# Power_-_Switch_Power.net
KiCad netlist of a schematic drawn in Altium Designer
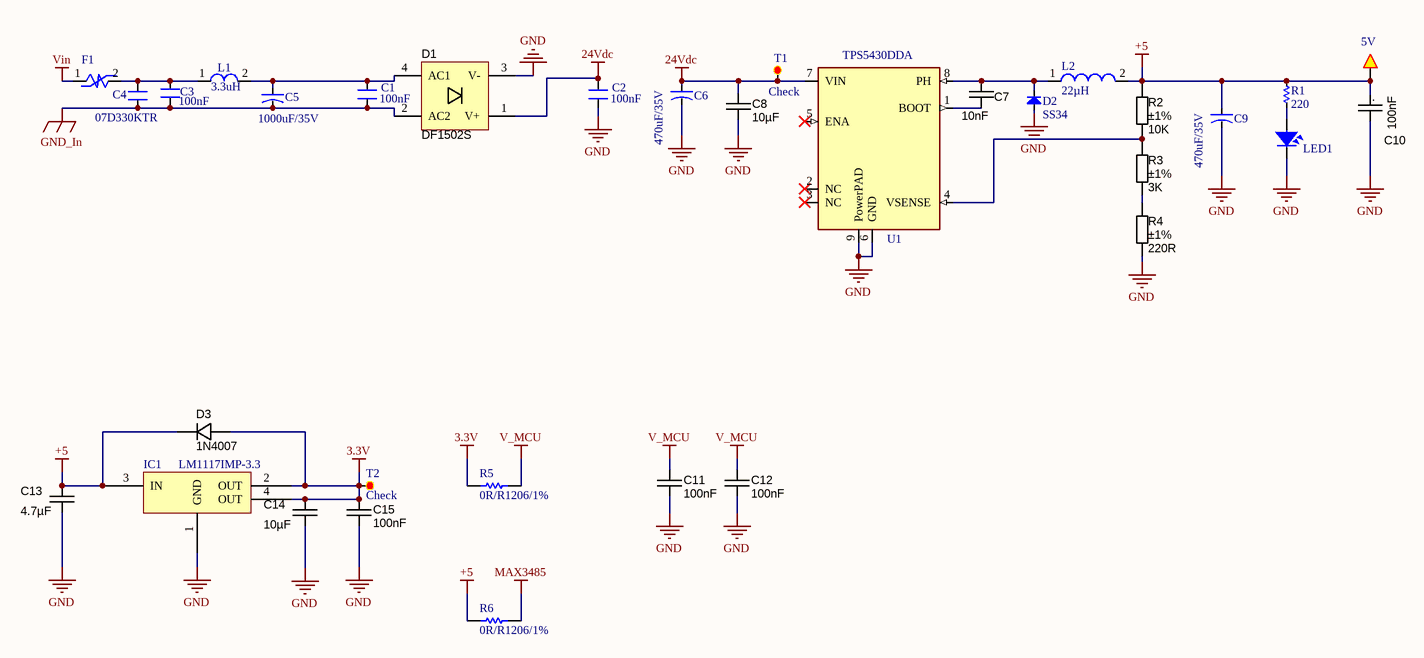
[diagram p0: Power - Switch Power.SchDoc]

(export (version "E")
  (design (tool "Eeschema 10.0.6"))
  (components
    (comp (ref "C1") (value "100nF") (footprint "CN-SMD-1206") (libsource (lib "thu vien 3d") (part "CN")))
    (comp (ref "C2") (value "100nF") (footprint "CN-SMD-1206") (libsource (lib "thu vien 3d") (part "CN")))
    (comp (ref "C3") (value "100nF") (footprint "CN2.5") (libsource (lib "thu vien 3d") (part "CN")))
    (comp (ref "C4") (value "07D330KTR") (footprint "CN2-T") (libsource (lib "thu vien 3d") (part "CN")))
    (comp (ref "C5")
      (value "1000uF/35V")
      (footprint "CA-ALU-5L")
      (description "Capacitor (Semiconductor SIM Model)")
      (fields (field (name "PUBLISHER") "Altium Limited"))
      (libsource (lib "thu vien 3d") (part "CN-ALU-DIP"))
    )
    (comp (ref "C6")
      (value "470uF/35V")
      (footprint "CA-ALU-6.3")
      (description "Capacitor (Semiconductor SIM Model)")
      (fields (field (name "PUBLISHER") "Altium Limited"))
      (libsource (lib "thu vien 3d") (part "CN-ALU-DIP"))
    )
    (comp (ref "C7")
      (value "10nF")
      (footprint "CAPC1608X90N")
      (description "10000pF ±10% 50V Ceramic Capacitor X7R 0603 (1608 Metric)")
      (fields (field (name "TOLERANCE") "±10%"))
      (libsource (lib "SangMV") (part "CAPC_10000pF_0603_50V_10%"))
    )
    (comp (ref "C8")
      (value "10µF")
      (footprint "CAPC2012X135N")
      (description "10µF ±10% 50V Ceramic Capacitor X7R 1206 (3216 Metric)")
      (fields (field (name "TOLERANCE") "±10%") (field (name "MANUFACTURER PART NUMBER") "TMK316AB7106KLHT"))
      (libsource (lib "All Library") (part "CAPC_10uF_0805_X7R_25V_10%"))
    )
    (comp (ref "C9")
      (value "470uF/35V")
      (footprint "CA-ALU-6.3")
      (description "Capacitor (Semiconductor SIM Model)")
      (fields (field (name "PUBLISHER") "Altium Limited"))
      (libsource (lib "thu vien 3d") (part "CN-ALU-DIP"))
    )
    (comp (ref "C10")
      (value "100nF")
      (footprint "CAPC2012X135N")
      (description "0.1µF ±10% 50V Ceramic Capacitor X7R 0805 (2012 Metric)")
      (fields (field (name "TOLERANCE") "±10%") (field (name "MANUFACTURER PART NUMBER") "CL21B104KBFXPJE"))
      (libsource (lib "SangMV") (part "CAPC_100nF_0805_X7R_50V_10%"))
    )
    (comp (ref "C11")
      (value "100nF")
      (footprint "CAPC1608X90N")
      (description "0.1µF ±10% 50V Ceramic Capacitor X7R 0603 (1608 Metric)")
      (fields (field (name "TOLERANCE") "±10%"))
      (libsource (lib "All Library") (part "CAPC_100nF_0603_X7R_50V_10%"))
    )
    (comp (ref "C12")
      (value "100nF")
      (footprint "CAPC1608X90N")
      (description "0.1µF ±10% 50V Ceramic Capacitor X7R 0603 (1608 Metric)")
      (fields (field (name "TOLERANCE") "±10%"))
      (libsource (lib "All Library") (part "CAPC_100nF_0603_X7R_50V_10%"))
    )
    (comp (ref "C13")
      (value "4.7µF")
      (footprint "CAPC2012X135N")
      (description "4.7µF ±10% 50V Ceramic Capacitor X7R 0805 (2012 Metric)")
      (fields
        (field (name "TOLERANCE") "±10%")
        (field (name "MANUFACTURER PART NUMBER") "CGA4J1X7R1H475K125AE")
      )
      (libsource (lib "All Library") (part "CAPC_4.7uF_0805_X7R_50V_10%"))
    )
    (comp (ref "C14")
      (value "10µF")
      (footprint "CAPC2012X135N")
      (description "4.7µF ±10% 50V Ceramic Capacitor X7R 0805 (2012 Metric)")
      (fields
        (field (name "TOLERANCE") "±10%")
        (field (name "MANUFACTURER PART NUMBER") "CGA4J1X7R1H475K125AE")
      )
      (libsource (lib "All Library") (part "CAPC_4.7uF_0805_X7R_50V_10%"))
    )
    (comp (ref "C15")
      (value "100nF")
      (footprint "CAPC1608X90N")
      (description "0.1µF ±10% 50V Ceramic Capacitor X7R 0603 (1608 Metric)")
      (fields (field (name "TOLERANCE") "±10%"))
      (libsource (lib "All Library") (part "CAPC_100nF_0603_X7R_50V_10%"))
    )
    (comp (ref "Check1")
      (value "5V")
      (footprint "SMD-2")
      (description "WR-PHD 2.54 mm Angled Socket Header")
      (fields
        (field (name "MANUFACTURER") "Würth Elektronik eiSos GmbH")
        (field (name "PARTNO") "613002143121")
        (field (name "CREATED BY") "Karrer Zheng")
      )
      (libsource (lib "Nichietsuvn") (part "Test"))
    )
    (comp (ref "D1")
      (value "DF1502S")
      (footprint "DIODE_DF_S")
      (description "Bridge Rectifier Single Phase Standard 200V Surface Mount DF-S")
      (libsource (lib "PCB_ESP32_Extern") (part "DIODE_DF1502S"))
    )
    (comp (ref "D2")
      (value "SS34")
      (footprint "DIO-SMD-106")
      (description "Default Diode")
      (fields (field (name "PUBLISHER") "Altium Limited"))
      (libsource (lib "thu vien 3d") (part "Diode SMD"))
    )
    (comp (ref "D3")
      (value "1N4007")
      (footprint "DO-214AC")
      (description "Diode  Standard Rectifier SMD 1000V 1A SMA")
      (libsource (lib "All Library") (part "DIODE_1N4007"))
    )
    (comp (ref "F1") (value "RUEF185") (footprint "RUEF165") (libsource (lib "All Library") (part "RUEF185")))
    (comp (ref "IC1")
      (value "LM1117IMP-3.3")
      (footprint "SOT223")
      (description "Linear Voltage Regulator IC  1 Output  800mA SOT-223")
      (fields
        (field (name "MANUFACTURER") "Texas Instruments")
        (field (name "MANUFACTURER PART NUMBER") "LM1117IMP-3.3/NOPB")
      )
      (libsource (lib "All Library") (part "IC_LM1117IMP-3.3"))
    )
    (comp (ref "L1")
      (value "3.3uH")
      (footprint "L-SMD-M-7.3x4.5")
      (fields
        (field (name "PARTNO") "78477010")
        (field (name "MANUFACTURER") "Wurth Elektronik")
        (field (name "CREATED BY") "Baojun Chen")
      )
      (libsource (lib "thu vien 3d") (part "L-SMD-1"))
    )
    (comp (ref "L2")
      (value "22µH")
      (footprint "IND_COIL_8D43")
      (description "22µH Shielded Wirewound Inductor 950mA 380mOhm Max Nonstandard")
      (libsource (lib "SangMV") (part "INDC_SMD_22uH_8D43"))
    )
    (comp (ref "LED1")
      (value "LED")
      (footprint "LED-0805-Blue")
      (libsource (lib "thu vien 3d") (part "LED SMD"))
    )
    (comp (ref "R1")
      (value "220")
      (footprint "RES-SMD-0603")
      (description "Resistor")
      (fields
        (field (name "MANUFACTURER") "Generic Components")
        (field (name "PUBLISHER") "Altium Hobart Technology Centre")
      )
      (libsource (lib "thu vien 3d") (part "Res-SMD"))
    )
    (comp (ref "R2")
      (value "10K")
      (footprint "RESC1608X55N")
      (fields
        (field (name "MANUFACTURER") "Stackpole Electronics Inc")
        (field (name "MANUFACTURER PART NUMBER") "RMCF0603FT10K0")
        (field (name "TOLERANCE") "±1%")
        (field (name "Comment") "10K_0603_1%")
      )
      (libsource (lib "SangMV") (part "RES_10K_0603_1%"))
    )
    (comp (ref "R3")
      (value "3K")
      (footprint "RESC1608X55N")
      (description "3 kOhms ±1% 0.1W, 1/10W Chip Resistor 0603 (1608 Metric) Automotive AEC-Q200 Thick Film")
      (fields
        (field (name "MANUFACTURER") "Stackpole Electronics Inc")
        (field (name "MANUFACTURER PART NUMBER") "RMCF0603FT3K00")
        (field (name "TOLERANCE") "±1%")
      )
      (libsource (lib "SangMV") (part "RES_3K_0603_1%"))
    )
    (comp (ref "R4")
      (value "220R")
      (footprint "RESC1608X55N")
      (description "220 Ohms ±1% 0.1W, 1/10W Chip Resistor 0603 (1608 Metric) Automotive AEC-Q200 Thick Film")
      (fields
        (field (name "MANUFACTURER") "Stackpole Electronics Inc")
        (field (name "MANUFACTURER PART NUMBER") "RMCF0603FT220R")
        (field (name "TOLERANCE") "±1%")
      )
      (libsource (lib "SangMV") (part "RES_220R_0603_1%"))
    )
    (comp (ref "R5")
      (value "0R/R1206/1%")
      (footprint "R1206")
      (description "RES SMD 0.0 OHM JUMPER 1/4W 1206")
      (fields
        (field (name "MANUFACTURER") "Bourns Inc.")
        (field (name "MANUFACTURER PART NUMBER") "CR1206-J/-000ELF")
      )
      (libsource (lib "All Library") (part "RES_0R/R1206/1%"))
    )
    (comp (ref "R6")
      (value "0R/R1206/1%")
      (footprint "R1206")
      (description "RES SMD 0.0 OHM JUMPER 1/4W 1206")
      (fields
        (field (name "MANUFACTURER") "Bourns Inc.")
        (field (name "MANUFACTURER PART NUMBER") "CR1206-J/-000ELF")
      )
      (libsource (lib "All Library") (part "RES_0R/R1206/1%"))
    )
    (comp (ref "T1")
      (value "Check")
      (footprint "SMD_1.5")
      (description "WR-PHD 2.54 mm Angled Socket Header")
      (fields
        (field (name "MANUFACTURER") "Würth Elektronik eiSos GmbH")
        (field (name "PARTNO") "613002143121")
        (field (name "CREATED BY") "Karrer Zheng")
      )
      (libsource (lib "All Library") (part "Test"))
    )
    (comp (ref "T2")
      (value "Check")
      (footprint "SMD_1.5")
      (description "WR-PHD 2.54 mm Angled Socket Header")
      (fields
        (field (name "MANUFACTURER") "Würth Elektronik eiSos GmbH")
        (field (name "PARTNO") "613002143121")
        (field (name "CREATED BY") "Karrer Zheng")
      )
      (libsource (lib "All Library") (part "Test"))
    )
    (comp (ref "U1")
      (value "TPS5430DDA")
      (footprint "TPS5430")
      (libsource (lib "Nichietsuvn") (part "TPS5430DDA"))
    )
  )
  (nets
    (net (code "1") (name "+5") (class "Default")
      (node (ref "C10") (pin "1") (pintype "passive"))
      (node (ref "C13") (pin "2") (pintype "passive"))
      (node (ref "C9") (pin "1") (pinfunction "1_1") (pintype "passive"))
      (node (ref "Check1") (pin "1") (pinfunction "1_1") (pintype "passive"))
      (node (ref "D3") (pin "C") (pinfunction "C_C") (pintype "passive"))
      (node (ref "IC1") (pin "3") (pinfunction "IN_3") (pintype "passive"))
      (node (ref "L2") (pin "2") (pinfunction "2_2") (pintype "passive"))
      (node (ref "R1") (pin "1") (pinfunction "1_1") (pintype "passive"))
      (node (ref "R2") (pin "2") (pinfunction "2_2") (pintype "passive"))
      (node (ref "R6") (pin "1") (pinfunction "1_1") (pintype "passive"))
    )
    (net (code "2") (name "3.3V") (class "Default")
      (node (ref "C14") (pin "2") (pintype "passive"))
      (node (ref "C15") (pin "1") (pintype "passive"))
      (node (ref "D3") (pin "A") (pinfunction "A_A") (pintype "passive"))
      (node (ref "IC1") (pin "2") (pinfunction "OUT_2") (pintype "passive"))
      (node (ref "IC1") (pin "4") (pinfunction "OUT_4") (pintype "passive"))
      (node (ref "R5") (pin "1") (pinfunction "1_1") (pintype "passive"))
      (node (ref "T2") (pin "1") (pinfunction "1_1") (pintype "passive"))
    )
    (net (code "3") (name "24Vdc") (class "Default")
      (node (ref "C2") (pin "2") (pinfunction "2_2") (pintype "passive"))
      (node (ref "C6") (pin "1") (pinfunction "1_1") (pintype "passive"))
      (node (ref "C8") (pin "2") (pintype "passive"))
      (node (ref "D1") (pin "1") (pinfunction "V+_1") (pintype "passive"))
      (node (ref "T1") (pin "1") (pinfunction "1_1") (pintype "passive"))
      (node (ref "U1") (pin "7") (pinfunction "VIN_7") (pintype "power_in"))
    )
    (net (code "4") (name "GND") (class "Default")
      (node (ref "C10") (pin "2") (pintype "passive"))
      (node (ref "C11") (pin "2") (pintype "passive"))
      (node (ref "C12") (pin "2") (pintype "passive"))
      (node (ref "C13") (pin "1") (pintype "passive"))
      (node (ref "C14") (pin "1") (pintype "passive"))
      (node (ref "C15") (pin "2") (pintype "passive"))
      (node (ref "C2") (pin "1") (pinfunction "1_1") (pintype "passive"))
      (node (ref "C6") (pin "2") (pinfunction "2_2") (pintype "passive"))
      (node (ref "C8") (pin "1") (pintype "passive"))
      (node (ref "C9") (pin "2") (pinfunction "2_2") (pintype "passive"))
      (node (ref "D1") (pin "3") (pinfunction "V-_3") (pintype "passive"))
      (node (ref "D2") (pin "1") (pinfunction "A_1") (pintype "passive"))
      (node (ref "IC1") (pin "1") (pinfunction "GND_1") (pintype "passive"))
      (node (ref "LED1") (pin "2") (pinfunction "2_2") (pintype "passive"))
      (node (ref "R4") (pin "1") (pinfunction "1_1") (pintype "passive"))
      (node (ref "U1") (pin "6") (pinfunction "GND_6") (pintype "power_in"))
      (node (ref "U1") (pin "9") (pinfunction "PowerPAD_9") (pintype "power_in"))
    )
    (net (code "5") (name "GND_In") (class "Default")
      (node (ref "C1") (pin "1") (pinfunction "1_1") (pintype "passive"))
      (node (ref "C3") (pin "1") (pinfunction "1_1") (pintype "passive"))
      (node (ref "C4") (pin "1") (pinfunction "1_1") (pintype "passive"))
      (node (ref "C5") (pin "2") (pinfunction "2_2") (pintype "passive"))
      (node (ref "D1") (pin "2") (pinfunction "AC2_2") (pintype "passive"))
    )
    (net (code "6") (name "MAX3485") (class "Default")
      (node (ref "R6") (pin "2") (pinfunction "2_2") (pintype "passive"))
    )
    (net (code "7") (name "Net-(C3-Pad2)") (class "Default")
      (node (ref "C3") (pin "2") (pinfunction "2_2") (pintype "passive"))
      (node (ref "C4") (pin "2") (pinfunction "2_2") (pintype "passive"))
      (node (ref "F1") (pin "2") (pinfunction "2_2") (pintype "passive"))
      (node (ref "L1") (pin "1") (pinfunction "1_1") (pintype "passive"))
    )
    (net (code "8") (name "Net-(D1-AC1)") (class "Default")
      (node (ref "C1") (pin "2") (pinfunction "2_2") (pintype "passive"))
      (node (ref "C5") (pin "1") (pinfunction "1_1") (pintype "passive"))
      (node (ref "D1") (pin "4") (pinfunction "AC1_4") (pintype "passive"))
      (node (ref "L1") (pin "2") (pinfunction "2_2") (pintype "passive"))
    )
    (net (code "9") (name "Net-(D2-K)") (class "Default")
      (node (ref "C7") (pin "2") (pintype "passive"))
      (node (ref "D2") (pin "2") (pinfunction "K_2") (pintype "passive"))
      (node (ref "L2") (pin "1") (pinfunction "1_1") (pintype "passive"))
      (node (ref "U1") (pin "8") (pinfunction "PH_8") (pintype "input"))
    )
    (net (code "10") (name "Net-(LED1-Pad1)") (class "Default")
      (node (ref "LED1") (pin "1") (pinfunction "1_1") (pintype "passive"))
      (node (ref "R1") (pin "2") (pinfunction "2_2") (pintype "passive"))
    )
    (net (code "11") (name "Net-(R3-Pad1)") (class "Default")
      (node (ref "R3") (pin "1") (pinfunction "1_1") (pintype "passive"))
      (node (ref "R4") (pin "2") (pinfunction "2_2") (pintype "passive"))
    )
    (net (code "12") (name "Net-(U1-BOOT)") (class "Default")
      (node (ref "C7") (pin "1") (pintype "passive"))
      (node (ref "U1") (pin "1") (pinfunction "BOOT_1") (pintype "output"))
    )
    (net (code "13") (name "Net-(U1-VSENSE)") (class "Default")
      (node (ref "R2") (pin "1") (pinfunction "1_1") (pintype "passive"))
      (node (ref "R3") (pin "2") (pinfunction "2_2") (pintype "passive"))
      (node (ref "U1") (pin "4") (pinfunction "VSENSE_4") (pintype "input"))
    )
    (net (code "14") (name "V_MCU") (class "Default")
      (node (ref "C11") (pin "1") (pintype "passive"))
      (node (ref "C12") (pin "1") (pintype "passive"))
      (node (ref "R5") (pin "2") (pinfunction "2_2") (pintype "passive"))
    )
    (net (code "15") (name "Vin") (class "Default")
      (node (ref "F1") (pin "1") (pinfunction "1_1") (pintype "passive"))
    )
    (net (code "16") (name "unconnected-(U1-ENA-Pad5)") (class "Default")
      (node (ref "U1") (pin "5") (pinfunction "ENA_5") (pintype "input+no_connect"))
    )
    (net (code "17") (name "unconnected-(U1-NC-Pad2)") (class "Default")
      (node (ref "U1") (pin "2") (pinfunction "NC_2") (pintype "passive+no_connect"))
    )
    (net (code "18") (name "unconnected-(U1-NC-Pad3)") (class "Default")
      (node (ref "U1") (pin "3") (pinfunction "NC_3") (pintype "passive+no_connect"))
    )
  )
)
